# GPS_radiologger_v4.net
KiCad netlist of a schematic drawn in EAGLE
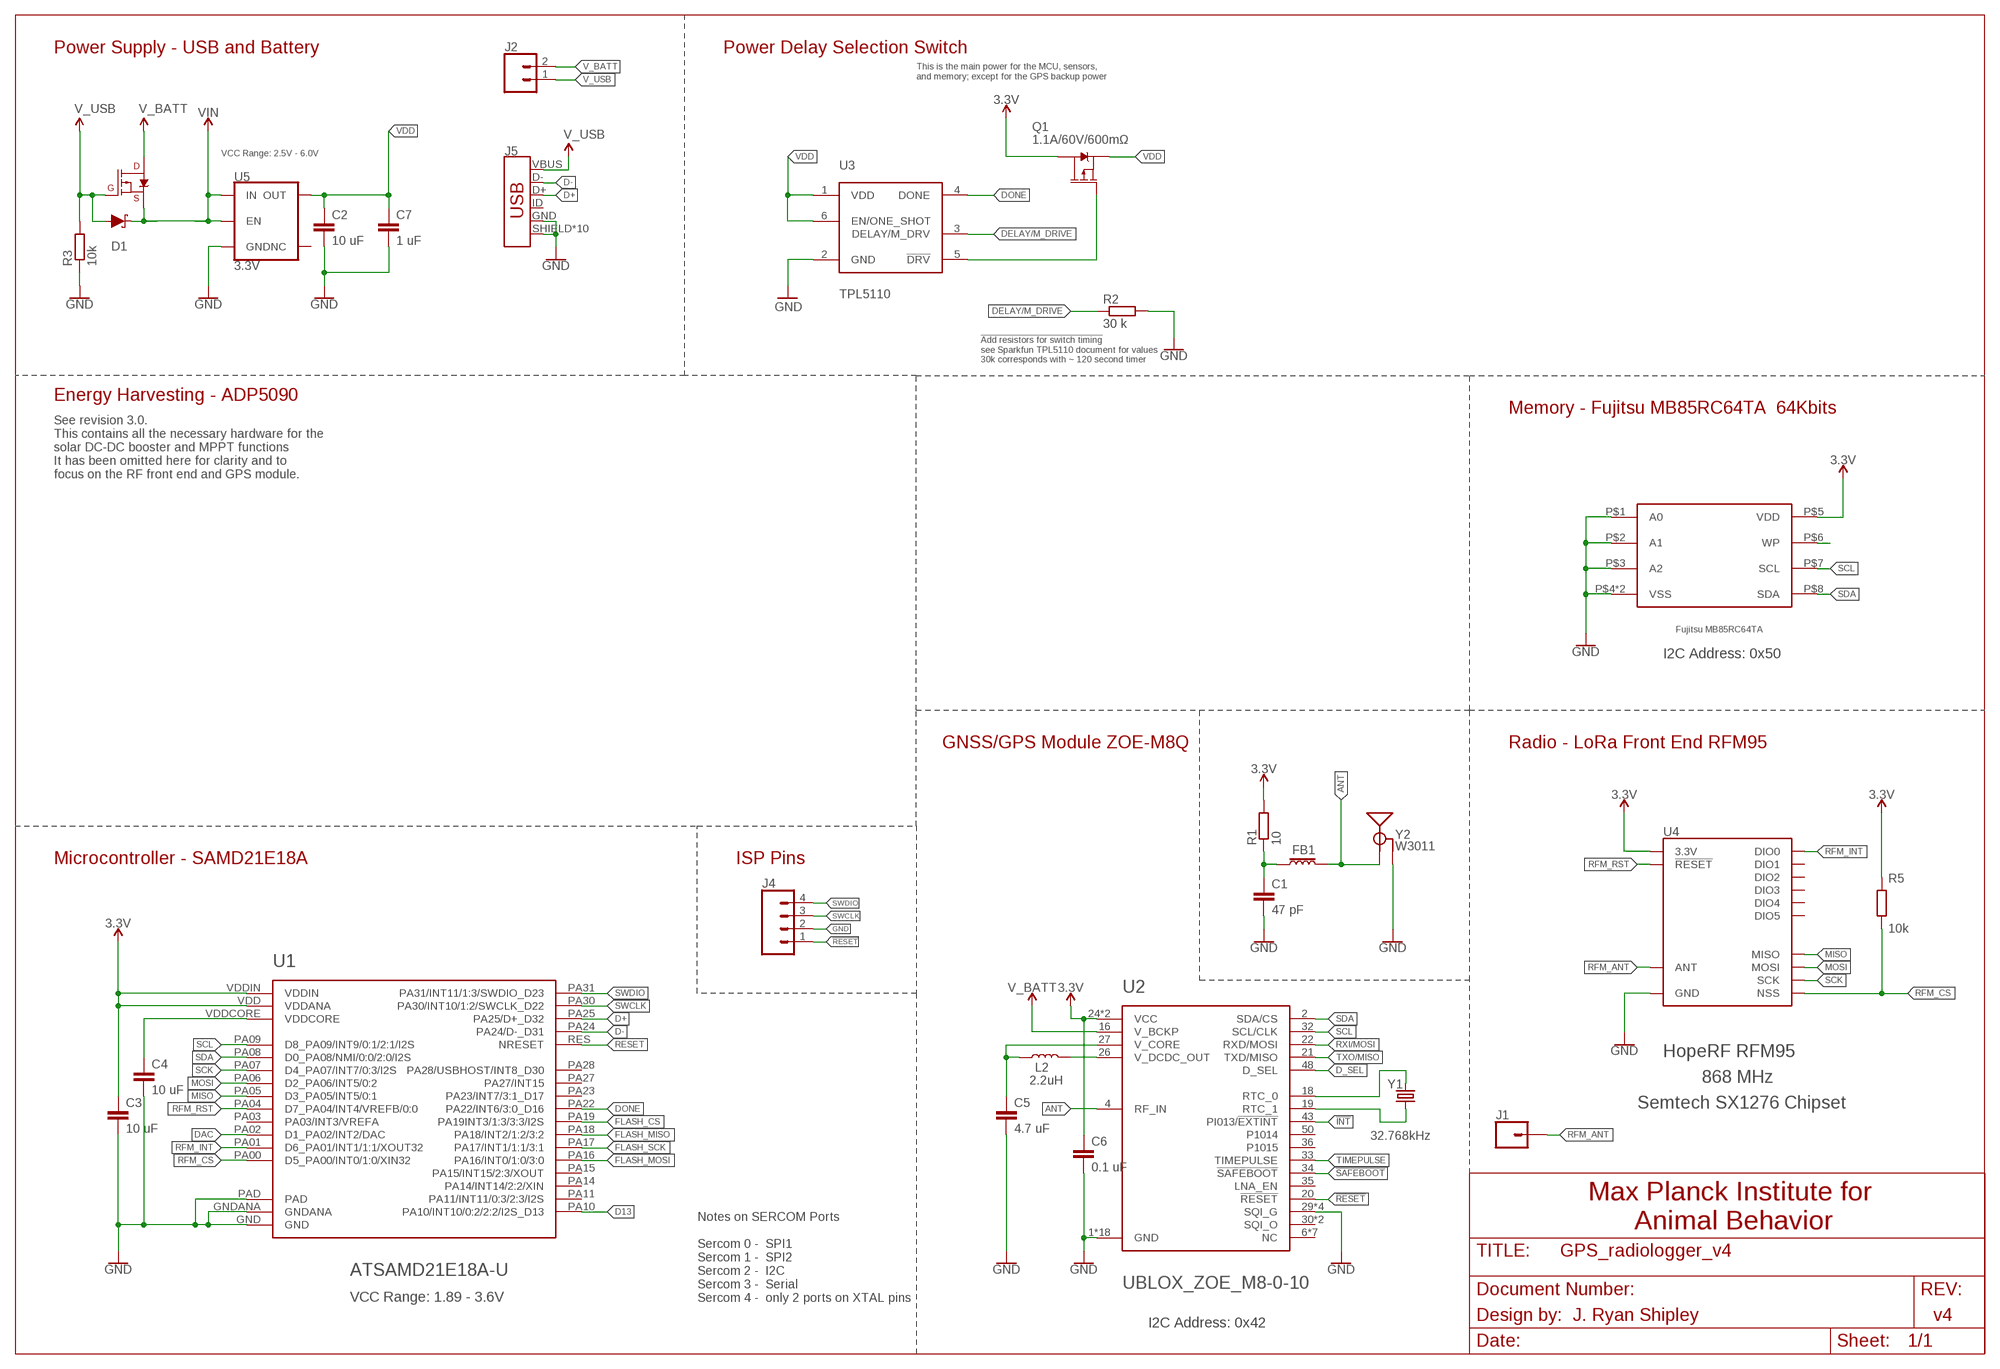
[diagram p0: schematic, sheet 1]

(export (version "E")
  (design (tool "Eeschema 10.0.6"))
  (components
    (comp (ref "C1")
      (value "47 pF")
      (footprint "eagle-import:C0201")
      (libsource (lib "eagle-import") (part "C-EUC0201"))
    )
    (comp (ref "C2")
      (value "10 uF")
      (footprint "eagle-import:C0201")
      (libsource (lib "eagle-import") (part "C-EUC0201"))
    )
    (comp (ref "C3")
      (value "10 uF")
      (footprint "eagle-import:C0201")
      (libsource (lib "eagle-import") (part "C-EUC0201"))
    )
    (comp (ref "C4")
      (value "10 uF")
      (footprint "eagle-import:C0201")
      (libsource (lib "eagle-import") (part "C-EUC0201"))
    )
    (comp (ref "C5")
      (value "4.7 uF")
      (footprint "eagle-import:C0201")
      (libsource (lib "eagle-import") (part "C-EUC0201"))
    )
    (comp (ref "C6")
      (value "0.1 uF")
      (footprint "eagle-import:C0201")
      (libsource (lib "eagle-import") (part "C-EUC0201"))
    )
    (comp (ref "C7")
      (value "1 uF")
      (footprint "eagle-import:C0201")
      (libsource (lib "eagle-import") (part "C-EUC0201"))
    )
    (comp (ref "D1")
      (value "1A/23V/620mV")
      (footprint "eagle-import:SOD-323")
      (libsource (lib "eagle-import") (part "DIODE-SCHOTTKY-BAT20J"))
    )
    (comp (ref "FB1")
      (value "FERRITE_BEAD-120_OHM-0402")
      (footprint "eagle-import:0402")
      (fields (field (name "MFG_PART") "BLM15HB121SN1D"))
      (libsource (lib "eagle-import") (part "FERRITE_BEAD-120_OHM-0402"))
    )
    (comp (ref "J1")
      (value "CONN_01OFFSET")
      (footprint "eagle-import:1X01_OFFSET")
      (libsource (lib "eagle-import") (part "CONN_01OFFSET"))
    )
    (comp (ref "J2")
      (value "CONN_02")
      (footprint "eagle-import:1X02")
      (libsource (lib "eagle-import") (part "CONN_02"))
    )
    (comp (ref "J4")
      (value "CONN_041.27MM_NO_SILK")
      (footprint "eagle-import:1X04_1.27MM_NO_SILK")
      (libsource (lib "eagle-import") (part "CONN_041.27MM_NO_SILK"))
    )
    (comp (ref "J5")
      (value "USB_MICRO-B_HALF_PTH_MILL")
      (footprint "eagle-import:USB-MICROB-PTH-MILL")
      (libsource (lib "eagle-import") (part "USB_MICRO-B_HALF_PTH_MILL"))
    )
    (comp (ref "L2")
      (value "2.2uH")
      (footprint "eagle-import:0806")
      (libsource (lib "eagle-import") (part "2.2μH_SHIELDED_INDUCTOR"))
    )
    (comp (ref "Q1")
      (value "1.1A/60V/600mΩ")
      (footprint "eagle-import:SOT23-3")
      (libsource (lib "eagle-import") (part "SparkFun-DiscreteSemi_514_MOSFET_PCH-SI2309DS"))
    )
    (comp (ref "Q2")
      (value "3.1A/30V/105mΩ")
      (footprint "eagle-import:SOT23-3")
      (libsource (lib "eagle-import") (part "MOSFET_PCH-DMG2307L"))
    )
    (comp (ref "R1")
      (value "10")
      (footprint "eagle-import:R0201")
      (libsource (lib "eagle-import") (part "R-EU_R0201"))
    )
    (comp (ref "R2")
      (value "30 k")
      (footprint "eagle-import:R0603")
      (libsource (lib "eagle-import") (part "R-EU_R0603"))
    )
    (comp (ref "R3")
      (value "10k")
      (footprint "eagle-import:R0201")
      (libsource (lib "eagle-import") (part "R-EU_R0201"))
    )
    (comp (ref "R5")
      (value "10k")
      (footprint "eagle-import:R0201")
      (libsource (lib "eagle-import") (part "R-EU_R0201"))
    )
    (comp (ref "U$2")
      (value "MB85RC64TA")
      (footprint "eagle-import:8-SON_2X3")
      (libsource (lib "eagle-import") (part "MB85RC64TA"))
    )
    (comp (ref "U1")
      (value "ATSAMD21E18A-U")
      (footprint "eagle-import:QFN-32_SAMD")
      (libsource (lib "eagle-import") (part "ATSAMD21E18A-U"))
    )
    (comp (ref "U2")
      (value "UBLOX_ZOE_M8-0-10")
      (footprint "eagle-import:UBLOX_ZOE_M8-0-10")
      (libsource (lib "eagle-import") (part "UBLOX_ZOE_M8-0-10"))
    )
    (comp (ref "U3")
      (value "TPL5110")
      (footprint "eagle-import:SOT23-6")
      (libsource (lib "eagle-import") (part "TPL5110"))
    )
    (comp (ref "U4")
      (value "RFM95W")
      (footprint "eagle-import:RFM95_96_97_98W")
      (libsource (lib "eagle-import") (part "RFM95W"))
    )
    (comp (ref "U5")
      (value "3.3V")
      (footprint "eagle-import:SOT23-5")
      (libsource (lib "eagle-import") (part "V_REG_AP2112K-3.3V"))
    )
    (comp (ref "Y1")
      (value "32.768kHz")
      (footprint "eagle-import:CRYSTAL-SMD-3.2X1.5MM")
      (libsource (lib "eagle-import") (part "CRYSTAL-32.768KHZSMD-3.2X1.5"))
    )
    (comp (ref "Y2")
      (value "W3011")
      (footprint "eagle-import:W3011")
      (libsource (lib "eagle-import") (part "GPS_CHIP_ANTENNAW3011"))
    )
  )
  (nets
    (net (code "1") (name "/~{INT}") (class "Default")
      (node (ref "U2") (pin "43") (pinfunction "PI013/~{EXTINT}_43") (pintype "bidirectional"))
    )
    (net (code "2") (name "/~{RESET}") (class "Default")
      (node (ref "J4") (pin "1") (pinfunction "1_1") (pintype "passive"))
      (node (ref "U2") (pin "20") (pinfunction "~{RESET}_20") (pintype "bidirectional"))
    )
    (net (code "3") (name "/~{SAFEBOOT}") (class "Default")
      (node (ref "U2") (pin "34") (pinfunction "~{SAFEBOOT}_34") (pintype "bidirectional"))
    )
    (net (code "4") (name "3.3V") (class "Default")
      (node (ref "C3") (pin "1") (pinfunction "1_1") (pintype "passive"))
      (node (ref "C6") (pin "1") (pinfunction "1_1") (pintype "passive"))
      (node (ref "Q1") (pin "3") (pinfunction "D_3") (pintype "bidirectional"))
      (node (ref "R1") (pin "2") (pinfunction "2_2") (pintype "passive"))
      (node (ref "R5") (pin "2") (pinfunction "2_2") (pintype "passive"))
      (node (ref "U$2") (pin "P$5") (pinfunction "VDD_P$5") (pintype "bidirectional"))
      (node (ref "U1") (pin "VDD") (pinfunction "VDDANA_VDD") (pintype "power_in"))
      (node (ref "U1") (pin "VDDIN") (pinfunction "VDDIN_VDDIN") (pintype "power_in"))
      (node (ref "U2") (pin "24") (pinfunction "VCC_24") (pintype "power_in"))
      (node (ref "U2") (pin "25") (pinfunction "VCC_25") (pintype "power_in"))
      (node (ref "U4") (pin "3.3V") (pinfunction "3.3V_3.3V") (pintype "bidirectional"))
    )
    (net (code "5") (name "ANT") (class "Default")
      (node (ref "FB1") (pin "1") (pinfunction "1_1") (pintype "passive"))
      (node (ref "U2") (pin "4") (pinfunction "RF_IN_4") (pintype "bidirectional"))
      (node (ref "Y2") (pin "1") (pinfunction "SIGNAL_1") (pintype "bidirectional"))
    )
    (net (code "6") (name "D+") (class "Default")
      (node (ref "J5") (pin "D+") (pinfunction "D+_D+") (pintype "bidirectional"))
      (node (ref "U1") (pin "PA25") (pinfunction "PA25/D+_D32_PA25") (pintype "bidirectional"))
    )
    (net (code "7") (name "D-") (class "Default")
      (node (ref "J5") (pin "D-") (pinfunction "D-_D-") (pintype "bidirectional"))
      (node (ref "U1") (pin "PA24") (pinfunction "PA24/D-_D31_PA24") (pintype "bidirectional"))
    )
    (net (code "8") (name "D13") (class "Default")
      (node (ref "U1") (pin "PA10") (pinfunction "PA10/INT10/0:2/2:2/I2S_D13_PA10") (pintype "bidirectional"))
    )
    (net (code "9") (name "DAC") (class "Default")
      (node (ref "U1") (pin "PA02") (pinfunction "D1_PA02/INT2/DAC_PA02") (pintype "bidirectional"))
    )
    (net (code "10") (name "DELAY{slash}M_DRIVE") (class "Default")
      (node (ref "R2") (pin "1") (pinfunction "1_1") (pintype "passive"))
      (node (ref "U3") (pin "3") (pinfunction "DELAY/M_DRV_3") (pintype "input"))
    )
    (net (code "11") (name "DONE") (class "Default")
      (node (ref "U1") (pin "PA22") (pinfunction "PA22/INT6/3:0_D16_PA22") (pintype "bidirectional"))
      (node (ref "U3") (pin "4") (pinfunction "DONE_4") (pintype "input"))
    )
    (net (code "12") (name "D_SEL") (class "Default")
      (node (ref "U2") (pin "48") (pinfunction "D_SEL_48") (pintype "bidirectional"))
    )
    (net (code "13") (name "FLASH_CS") (class "Default")
      (node (ref "U1") (pin "PA19") (pinfunction "PA19INT3/1:3/3:3/I2S_PA19") (pintype "bidirectional"))
    )
    (net (code "14") (name "FLASH_MISO") (class "Default")
      (node (ref "U1") (pin "PA18") (pinfunction "PA18/INT2/1:2/3:2_PA18") (pintype "bidirectional"))
    )
    (net (code "15") (name "FLASH_MOSI") (class "Default")
      (node (ref "U1") (pin "PA16") (pinfunction "PA16/INT0/1:0/3:0_PA16") (pintype "bidirectional"))
    )
    (net (code "16") (name "FLASH_SCK") (class "Default")
      (node (ref "U1") (pin "PA17") (pinfunction "PA17/INT1/1:1/3:1_PA17") (pintype "bidirectional"))
    )
    (net (code "17") (name "GND") (class "Default")
      (node (ref "C1") (pin "2") (pinfunction "2_2") (pintype "passive"))
      (node (ref "C2") (pin "2") (pinfunction "2_2") (pintype "passive"))
      (node (ref "C3") (pin "2") (pinfunction "2_2") (pintype "passive"))
      (node (ref "C4") (pin "2") (pinfunction "2_2") (pintype "passive"))
      (node (ref "C5") (pin "2") (pinfunction "2_2") (pintype "passive"))
      (node (ref "C6") (pin "2") (pinfunction "2_2") (pintype "passive"))
      (node (ref "C7") (pin "2") (pinfunction "2_2") (pintype "passive"))
      (node (ref "J4") (pin "2") (pinfunction "2_2") (pintype "passive"))
      (node (ref "J5") (pin "GND") (pinfunction "GND_GND") (pintype "power_in"))
      (node (ref "J5") (pin "SHIELD") (pinfunction "SHIELD_SHIELD") (pintype "bidirectional"))
      (node (ref "J5") (pin "SHIELD10") (pinfunction "SHIELD_SHIELD10") (pintype "bidirectional"))
      (node (ref "J5") (pin "SHIELD2") (pinfunction "SHIELD_SHIELD2") (pintype "bidirectional"))
      (node (ref "J5") (pin "SHIELD3") (pinfunction "SHIELD_SHIELD3") (pintype "bidirectional"))
      (node (ref "J5") (pin "SHIELD4") (pinfunction "SHIELD_SHIELD4") (pintype "bidirectional"))
      (node (ref "J5") (pin "SHIELD5") (pinfunction "SHIELD_SHIELD5") (pintype "bidirectional"))
      (node (ref "J5") (pin "SHIELD6") (pinfunction "SHIELD_SHIELD6") (pintype "bidirectional"))
      (node (ref "J5") (pin "SHIELD7") (pinfunction "SHIELD_SHIELD7") (pintype "bidirectional"))
      (node (ref "J5") (pin "SHIELD8") (pinfunction "SHIELD_SHIELD8") (pintype "bidirectional"))
      (node (ref "J5") (pin "SHIELD9") (pinfunction "SHIELD_SHIELD9") (pintype "bidirectional"))
      (node (ref "R2") (pin "2") (pinfunction "2_2") (pintype "passive"))
      (node (ref "R3") (pin "1") (pinfunction "1_1") (pintype "passive"))
      (node (ref "U$2") (pin "P$1") (pinfunction "A0_P$1") (pintype "bidirectional"))
      (node (ref "U$2") (pin "P$2") (pinfunction "A1_P$2") (pintype "bidirectional"))
      (node (ref "U$2") (pin "P$3") (pinfunction "A2_P$3") (pintype "bidirectional"))
      (node (ref "U$2") (pin "P$4") (pinfunction "VSS_P$4") (pintype "bidirectional"))
      (node (ref "U$2") (pin "P$9") (pinfunction "VSS_P$9") (pintype "bidirectional"))
      (node (ref "U1") (pin "GND") (pinfunction "GND_GND") (pintype "power_in"))
      (node (ref "U1") (pin "GNDANA") (pinfunction "GNDANA_GNDANA") (pintype "power_in"))
      (node (ref "U1") (pin "PAD") (pinfunction "PAD_PAD") (pintype "power_in"))
      (node (ref "U2") (pin "1") (pinfunction "GND_1") (pintype "power_in"))
      (node (ref "U2") (pin "10") (pinfunction "GND_10") (pintype "power_in"))
      (node (ref "U2") (pin "11") (pinfunction "GND_11") (pintype "power_in"))
      (node (ref "U2") (pin "12") (pinfunction "GND_12") (pintype "power_in"))
      (node (ref "U2") (pin "17") (pinfunction "GND_17") (pintype "power_in"))
      (node (ref "U2") (pin "23") (pinfunction "GND_23") (pintype "power_in"))
      (node (ref "U2") (pin "29") (pinfunction "SQI_G_29") (pintype "bidirectional"))
      (node (ref "U2") (pin "3") (pinfunction "GND_3") (pintype "power_in"))
      (node (ref "U2") (pin "31") (pinfunction "SQI_G_31") (pintype "bidirectional"))
      (node (ref "U2") (pin "37") (pinfunction "GND_37") (pintype "power_in"))
      (node (ref "U2") (pin "38") (pinfunction "GND_38") (pintype "power_in"))
      (node (ref "U2") (pin "39") (pinfunction "GND_39") (pintype "power_in"))
      (node (ref "U2") (pin "40") (pinfunction "GND_40") (pintype "power_in"))
      (node (ref "U2") (pin "41") (pinfunction "GND_41") (pintype "power_in"))
      (node (ref "U2") (pin "44") (pinfunction "GND_44") (pintype "power_in"))
      (node (ref "U2") (pin "46") (pinfunction "SQI_G_46") (pintype "bidirectional"))
      (node (ref "U2") (pin "47") (pinfunction "SQI_G_47") (pintype "bidirectional"))
      (node (ref "U2") (pin "49") (pinfunction "GND_49") (pintype "power_in"))
      (node (ref "U2") (pin "5") (pinfunction "GND_5") (pintype "power_in"))
      (node (ref "U2") (pin "7") (pinfunction "GND_7") (pintype "power_in"))
      (node (ref "U2") (pin "8") (pinfunction "GND_8") (pintype "power_in"))
      (node (ref "U2") (pin "9") (pinfunction "GND_9") (pintype "power_in"))
      (node (ref "U3") (pin "2") (pinfunction "GND_2") (pintype "power_in"))
      (node (ref "U4") (pin "GND@1") (pinfunction "GND_GND@1") (pintype "bidirectional"))
      (node (ref "U4") (pin "GND@2") (pinfunction "GND_GND@2") (pintype "bidirectional"))
      (node (ref "U4") (pin "GND@3") (pinfunction "GND_GND@3") (pintype "bidirectional"))
      (node (ref "U5") (pin "2") (pinfunction "GND_2") (pintype "input"))
      (node (ref "Y2") (pin "2") (pinfunction "GND_2") (pintype "bidirectional"))
      (node (ref "Y2") (pin "3") (pinfunction "GND_3") (pintype "bidirectional"))
    )
    (net (code "18") (name "MISO") (class "Default")
      (node (ref "U1") (pin "PA05") (pinfunction "D3_PA05/INT5/0:1_PA05") (pintype "bidirectional"))
      (node (ref "U4") (pin "MISO") (pinfunction "MISO_MISO") (pintype "bidirectional"))
    )
    (net (code "19") (name "MOSI") (class "Default")
      (node (ref "U1") (pin "PA06") (pinfunction "D2_PA06/INT5/0:2_PA06") (pintype "bidirectional"))
      (node (ref "U4") (pin "MOSI") (pinfunction "MOSI_MOSI") (pintype "bidirectional"))
    )
    (net (code "20") (name "Net-(C1-Pad1)") (class "Default")
      (node (ref "C1") (pin "1") (pinfunction "1_1") (pintype "passive"))
      (node (ref "FB1") (pin "2") (pinfunction "2_2") (pintype "passive"))
      (node (ref "R1") (pin "1") (pinfunction "1_1") (pintype "passive"))
    )
    (net (code "21") (name "Net-(C4-Pad1)") (class "Default")
      (node (ref "C4") (pin "1") (pinfunction "1_1") (pintype "passive"))
      (node (ref "U1") (pin "VDDCORE") (pinfunction "VDDCORE_VDDCORE") (pintype "power_in"))
    )
    (net (code "22") (name "Net-(Q1-G)") (class "Default")
      (node (ref "Q1") (pin "1") (pinfunction "G_1") (pintype "bidirectional"))
      (node (ref "U3") (pin "5") (pinfunction "~{DRV}_5") (pintype "output"))
    )
    (net (code "23") (name "Net-(U2-RTC_0)") (class "Default")
      (node (ref "U2") (pin "18") (pinfunction "RTC_0_18") (pintype "bidirectional"))
      (node (ref "Y1") (pin "P$2") (pinfunction "2_P$2") (pintype "passive"))
    )
    (net (code "24") (name "Net-(U2-RTC_1)") (class "Default")
      (node (ref "U2") (pin "19") (pinfunction "RTC_1_19") (pintype "bidirectional"))
      (node (ref "Y1") (pin "P$1") (pinfunction "1_P$1") (pintype "passive"))
    )
    (net (code "25") (name "Net-(U2-V_CORE)") (class "Default")
      (node (ref "C5") (pin "1") (pinfunction "1_1") (pintype "passive"))
      (node (ref "L2") (pin "1") (pinfunction "1_1") (pintype "passive"))
      (node (ref "U2") (pin "27") (pinfunction "V_CORE_27") (pintype "power_in"))
    )
    (net (code "26") (name "Net-(U2-V_DCDC_OUT)") (class "Default")
      (node (ref "L2") (pin "2") (pinfunction "2_2") (pintype "passive"))
      (node (ref "U2") (pin "26") (pinfunction "V_DCDC_OUT_26") (pintype "power_in"))
    )
    (net (code "27") (name "RESET") (class "Default")
      (node (ref "U1") (pin "RES") (pinfunction "NRESET_RES") (pintype "bidirectional"))
    )
    (net (code "28") (name "RFM_ANT") (class "Default")
      (node (ref "J1") (pin "1") (pinfunction "1_1") (pintype "passive"))
      (node (ref "U4") (pin "ANT") (pinfunction "ANT_ANT") (pintype "bidirectional"))
    )
    (net (code "29") (name "RFM_CS") (class "Default")
      (node (ref "R5") (pin "1") (pinfunction "1_1") (pintype "passive"))
      (node (ref "U1") (pin "PA00") (pinfunction "D5_PA00/INT0/1:0/XIN32_PA00") (pintype "bidirectional"))
      (node (ref "U4") (pin "NSS") (pinfunction "NSS_NSS") (pintype "bidirectional"))
    )
    (net (code "30") (name "RFM_INT") (class "Default")
      (node (ref "U1") (pin "PA01") (pinfunction "D6_PA01/INT1/1:1/XOUT32_PA01") (pintype "bidirectional"))
      (node (ref "U4") (pin "DIO0") (pinfunction "DIO0_DIO0") (pintype "bidirectional"))
    )
    (net (code "31") (name "RFM_RST") (class "Default")
      (node (ref "U1") (pin "PA04") (pinfunction "D7_PA04/INT4/VREFB/0:0_PA04") (pintype "bidirectional"))
      (node (ref "U4") (pin "!RESET") (pinfunction "~{RESET}_!RESET") (pintype "bidirectional"))
    )
    (net (code "32") (name "RXI{slash}MOSI") (class "Default")
      (node (ref "U2") (pin "22") (pinfunction "RXD/MOSI_22") (pintype "bidirectional"))
    )
    (net (code "33") (name "SCK") (class "Default")
      (node (ref "U1") (pin "PA07") (pinfunction "D4_PA07/INT7/0:3/I2S_PA07") (pintype "bidirectional"))
      (node (ref "U4") (pin "SCK") (pinfunction "SCK_SCK") (pintype "bidirectional"))
    )
    (net (code "34") (name "SCL") (class "Default")
      (node (ref "U$2") (pin "P$7") (pinfunction "SCL_P$7") (pintype "bidirectional"))
      (node (ref "U1") (pin "PA09") (pinfunction "D8_PA09/INT9/0:1/2:1/I2S_PA09") (pintype "bidirectional"))
      (node (ref "U2") (pin "32") (pinfunction "SCL/CLK_32") (pintype "bidirectional"))
    )
    (net (code "35") (name "SDA") (class "Default")
      (node (ref "U$2") (pin "P$8") (pinfunction "SDA_P$8") (pintype "bidirectional"))
      (node (ref "U1") (pin "PA08") (pinfunction "D0_PA08/NMI/0:0/2:0/I2S_PA08") (pintype "bidirectional"))
      (node (ref "U2") (pin "2") (pinfunction "SDA/CS_2") (pintype "bidirectional"))
    )
    (net (code "36") (name "SWCLK") (class "Default")
      (node (ref "J4") (pin "3") (pinfunction "3_3") (pintype "passive"))
      (node (ref "U1") (pin "PA30") (pinfunction "PA30/INT10/1:2/SWCLK_D22_PA30") (pintype "bidirectional"))
    )
    (net (code "37") (name "SWDIO") (class "Default")
      (node (ref "J4") (pin "4") (pinfunction "4_4") (pintype "passive"))
      (node (ref "U1") (pin "PA31") (pinfunction "PA31/INT11/1:3/SWDIO_D23_PA31") (pintype "bidirectional"))
    )
    (net (code "38") (name "TIMEPULSE") (class "Default")
      (node (ref "U2") (pin "33") (pinfunction "TIMEPULSE_33") (pintype "bidirectional"))
    )
    (net (code "39") (name "TXO{slash}MISO") (class "Default")
      (node (ref "U2") (pin "21") (pinfunction "TXD/MISO_21") (pintype "bidirectional"))
    )
    (net (code "40") (name "VDD") (class "Default")
      (node (ref "C2") (pin "1") (pinfunction "1_1") (pintype "passive"))
      (node (ref "C7") (pin "1") (pinfunction "1_1") (pintype "passive"))
      (node (ref "Q1") (pin "2") (pinfunction "S_2") (pintype "bidirectional"))
      (node (ref "U3") (pin "1") (pinfunction "VDD_1") (pintype "power_in"))
      (node (ref "U3") (pin "6") (pinfunction "EN/ONE_SHOT_6") (pintype "input"))
      (node (ref "U5") (pin "5") (pinfunction "OUT_5") (pintype "passive"))
    )
    (net (code "41") (name "VIN") (class "Default")
      (node (ref "D1") (pin "C") (pinfunction "C_C") (pintype "passive"))
      (node (ref "Q2") (pin "2") (pinfunction "S_2") (pintype "bidirectional"))
      (node (ref "U5") (pin "1") (pinfunction "IN_1") (pintype "input"))
      (node (ref "U5") (pin "3") (pinfunction "EN_3") (pintype "input"))
    )
    (net (code "42") (name "V_BATT") (class "Default")
      (node (ref "J2") (pin "2") (pinfunction "2_2") (pintype "passive"))
      (node (ref "Q2") (pin "3") (pinfunction "D_3") (pintype "bidirectional"))
      (node (ref "U2") (pin "16") (pinfunction "V_BCKP_16") (pintype "power_in"))
    )
    (net (code "43") (name "V_USB") (class "Default")
      (node (ref "D1") (pin "A") (pinfunction "A_A") (pintype "passive"))
      (node (ref "J2") (pin "1") (pinfunction "1_1") (pintype "passive"))
      (node (ref "J5") (pin "VBUS") (pinfunction "VBUS_VBUS") (pintype "power_in"))
      (node (ref "Q2") (pin "1") (pinfunction "G_1") (pintype "bidirectional"))
      (node (ref "R3") (pin "2") (pinfunction "2_2") (pintype "passive"))
    )
    (net (code "44") (name "unconnected-(J5-PadID)") (class "Default")
      (node (ref "J5") (pin "ID") (pinfunction "ID_ID") (pintype "bidirectional"))
    )
    (net (code "45") (name "unconnected-(U$2-WP-PadP$6)") (class "Default")
      (node (ref "U$2") (pin "P$6") (pinfunction "WP_P$6") (pintype "bidirectional"))
    )
    (net (code "46") (name "unconnected-(U1-PA03{slash}INT3{slash}VREFA-PadPA03)") (class "Default")
      (node (ref "U1") (pin "PA03") (pinfunction "PA03/INT3/VREFA_PA03") (pintype "bidirectional"))
    )
    (net (code "47") (name "unconnected-(U1-PA11{slash}INT11{slash}0:3{slash}2:3{slash}I2S-PadPA11)") (class "Default")
      (node (ref "U1") (pin "PA11") (pinfunction "PA11/INT11/0:3/2:3/I2S_PA11") (pintype "bidirectional"))
    )
    (net (code "48") (name "unconnected-(U1-PA14{slash}INT14{slash}2:2{slash}XIN-PadPA14)") (class "Default")
      (node (ref "U1") (pin "PA14") (pinfunction "PA14/INT14/2:2/XIN_PA14") (pintype "bidirectional"))
    )
    (net (code "49") (name "unconnected-(U1-PA15{slash}INT15{slash}2:3{slash}XOUT-PadPA15)") (class "Default")
      (node (ref "U1") (pin "PA15") (pinfunction "PA15/INT15/2:3/XOUT_PA15") (pintype "bidirectional"))
    )
    (net (code "50") (name "unconnected-(U1-PA23{slash}INT7{slash}3:1_D17-PadPA23)") (class "Default")
      (node (ref "U1") (pin "PA23") (pinfunction "PA23/INT7/3:1_D17_PA23") (pintype "bidirectional"))
    )
    (net (code "51") (name "unconnected-(U1-PA27{slash}INT15-PadPA27)") (class "Default")
      (node (ref "U1") (pin "PA27") (pinfunction "PA27/INT15_PA27") (pintype "bidirectional"))
    )
    (net (code "52") (name "unconnected-(U1-PA28{slash}USBHOST{slash}INT8_D30-PadPA28)") (class "Default")
      (node (ref "U1") (pin "PA28") (pinfunction "PA28/USBHOST/INT8_D30_PA28") (pintype "bidirectional"))
    )
    (net (code "53") (name "unconnected-(U2-LNA_EN-Pad35)") (class "Default")
      (node (ref "U2") (pin "35") (pinfunction "LNA_EN_35") (pintype "bidirectional"))
    )
    (net (code "54") (name "unconnected-(U2-NC-Pad6)") (class "Default")
      (node (ref "U2") (pin "6") (pinfunction "NC_6") (pintype "no_connect"))
    )
    (net (code "55") (name "unconnected-(U2-NC-Pad13)") (class "Default")
      (node (ref "U2") (pin "13") (pinfunction "NC_13") (pintype "no_connect"))
    )
    (net (code "56") (name "unconnected-(U2-NC-Pad14)") (class "Default")
      (node (ref "U2") (pin "14") (pinfunction "NC_14") (pintype "no_connect"))
    )
    (net (code "57") (name "unconnected-(U2-NC-Pad15)") (class "Default")
      (node (ref "U2") (pin "15") (pinfunction "NC_15") (pintype "no_connect"))
    )
    (net (code "58") (name "unconnected-(U2-NC-Pad28)") (class "Default")
      (node (ref "U2") (pin "28") (pinfunction "NC_28") (pintype "no_connect"))
    )
    (net (code "59") (name "unconnected-(U2-NC-Pad42)") (class "Default")
      (node (ref "U2") (pin "42") (pinfunction "NC_42") (pintype "no_connect"))
    )
    (net (code "60") (name "unconnected-(U2-NC-Pad51)") (class "Default")
      (node (ref "U2") (pin "51") (pinfunction "NC_51") (pintype "no_connect"))
    )
    (net (code "61") (name "unconnected-(U2-P1014-Pad50)") (class "Default")
      (node (ref "U2") (pin "50") (pinfunction "P1014_50") (pintype "bidirectional"))
    )
    (net (code "62") (name "unconnected-(U2-P1015-Pad36)") (class "Default")
      (node (ref "U2") (pin "36") (pinfunction "P1015_36") (pintype "bidirectional"))
    )
    (net (code "63") (name "unconnected-(U2-SQI_O-Pad30)") (class "Default")
      (node (ref "U2") (pin "30") (pinfunction "SQI_O_30") (pintype "no_connect"))
    )
    (net (code "64") (name "unconnected-(U2-SQI_O-Pad45)") (class "Default")
      (node (ref "U2") (pin "45") (pinfunction "SQI_O_45") (pintype "no_connect"))
    )
    (net (code "65") (name "unconnected-(U4-PadDIO1)") (class "Default")
      (node (ref "U4") (pin "DIO1") (pinfunction "DIO1_DIO1") (pintype "bidirectional"))
    )
    (net (code "66") (name "unconnected-(U4-PadDIO2)") (class "Default")
      (node (ref "U4") (pin "DIO2") (pinfunction "DIO2_DIO2") (pintype "bidirectional"))
    )
    (net (code "67") (name "unconnected-(U4-PadDIO3)") (class "Default")
      (node (ref "U4") (pin "DIO3") (pinfunction "DIO3_DIO3") (pintype "bidirectional"))
    )
    (net (code "68") (name "unconnected-(U4-PadDIO4)") (class "Default")
      (node (ref "U4") (pin "DIO4") (pinfunction "DIO4_DIO4") (pintype "bidirectional"))
    )
    (net (code "69") (name "unconnected-(U4-PadDIO5)") (class "Default")
      (node (ref "U4") (pin "DIO5") (pinfunction "DIO5_DIO5") (pintype "bidirectional"))
    )
    (net (code "70") (name "unconnected-(U5-NC-Pad4)") (class "Default")
      (node (ref "U5") (pin "4") (pinfunction "NC_4") (pintype "no_connect"))
    )
  )
)
